# LocoNet-DCC_Interface_v2_0.net
KiCad netlist of a schematic drawn in EAGLE
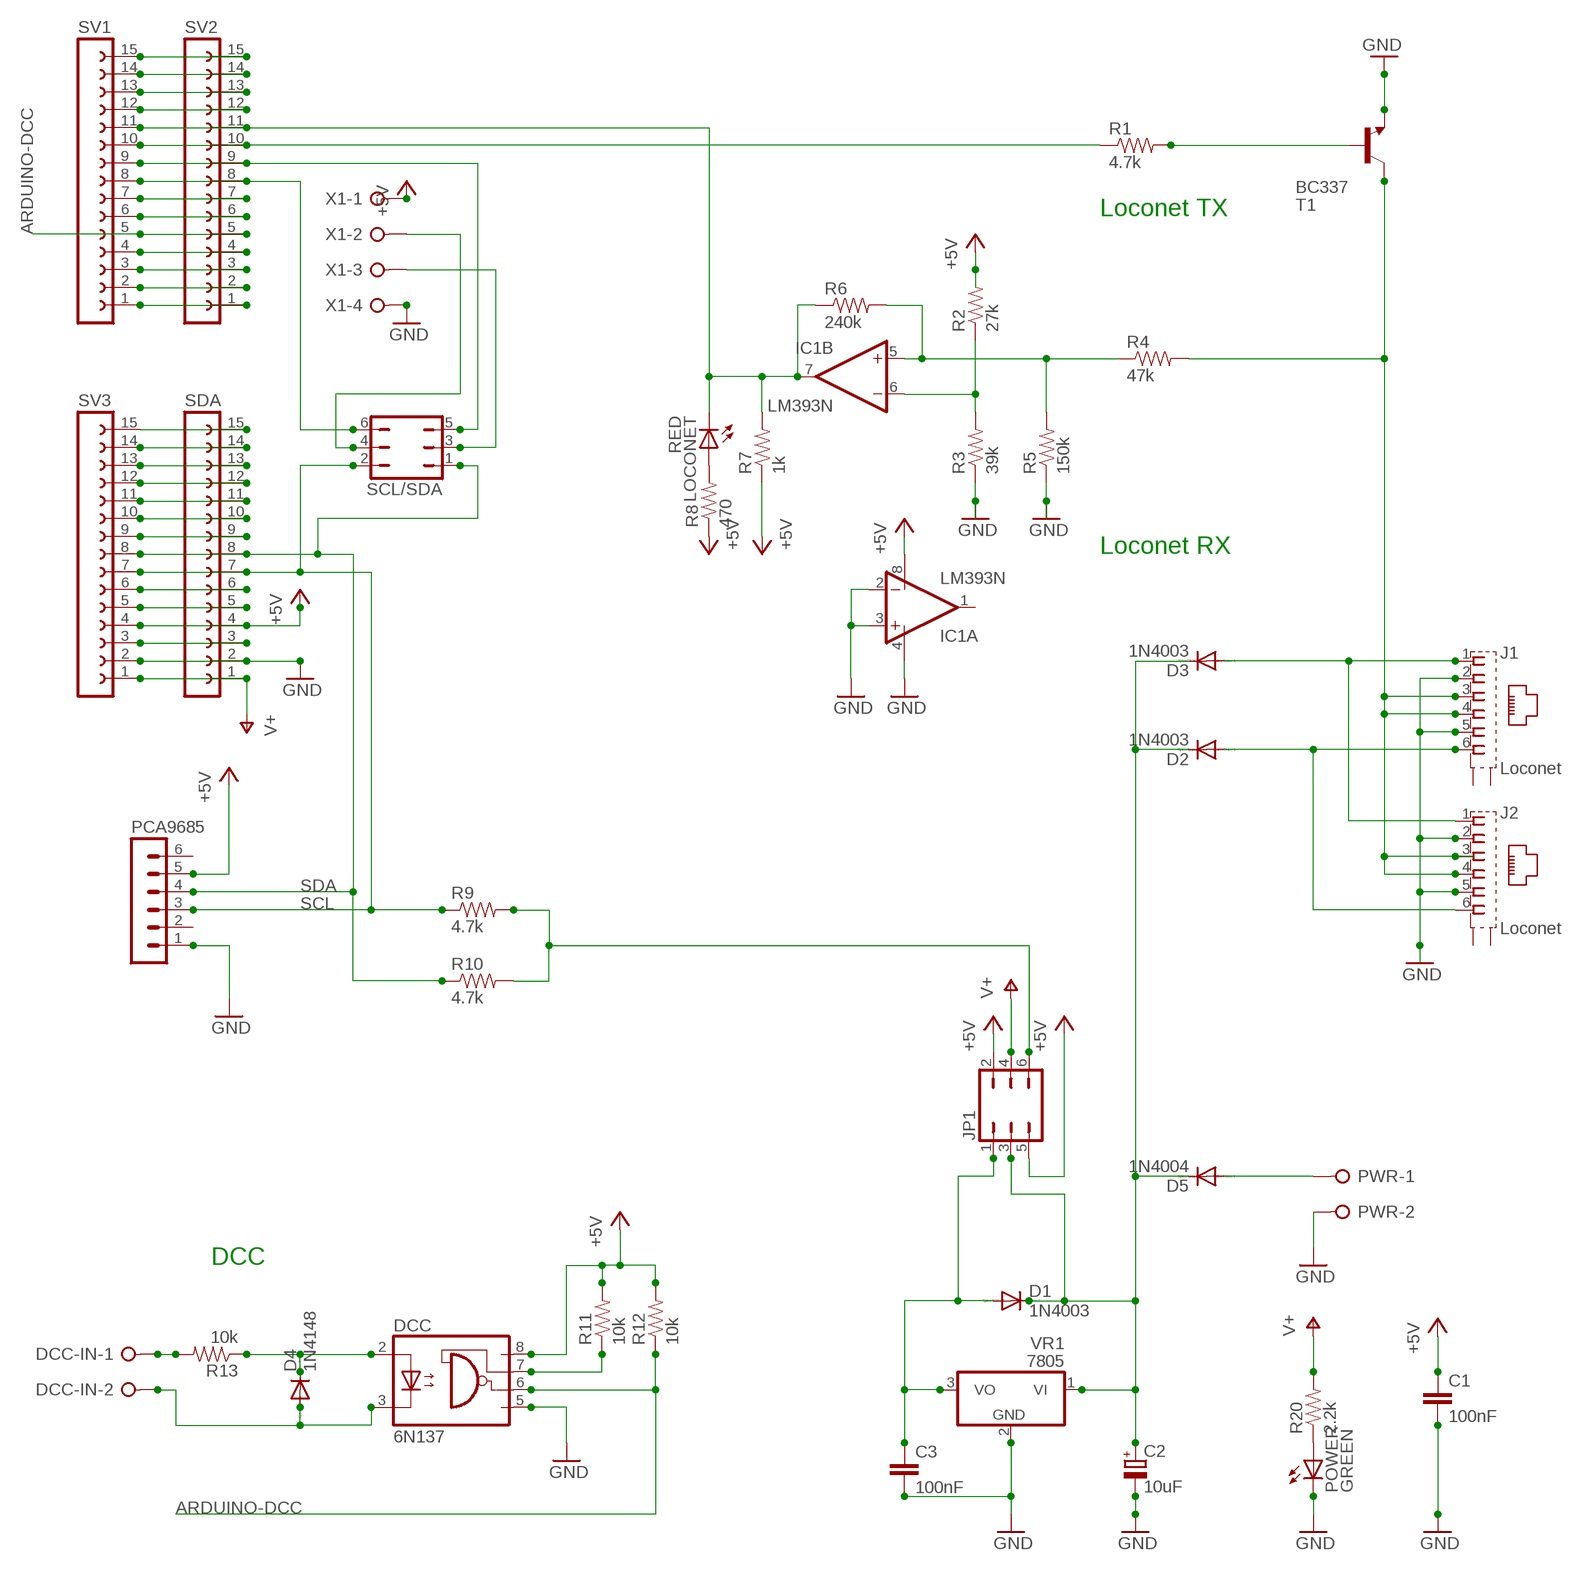
[diagram p0: schematic, sheet 1]

(export (version "E")
  (design (tool "Eeschema 10.0.6"))
  (components
    (comp (ref "C1")
      (value "100nF")
      (footprint "eagle-import:C025_050-025X075")
      (libsource (lib "eagle-import") (part "C-EU025_050-025X075"))
    )
    (comp (ref "C2")
      (value "10uF")
      (footprint "eagle-import:E2,5-6")
      (libsource (lib "eagle-import") (part "CPOL-EUE2.5-6"))
    )
    (comp (ref "C3")
      (value "100nF")
      (footprint "eagle-import:C025_050-025X075")
      (libsource (lib "eagle-import") (part "C-EU025_050-025X075"))
    )
    (comp (ref "D1")
      (value "1N4003")
      (footprint "eagle-import:DO41-10")
      (libsource (lib "eagle-import") (part "1N4004"))
    )
    (comp (ref "D2")
      (value "1N4003")
      (footprint "eagle-import:DO41-10")
      (libsource (lib "eagle-import") (part "1N4004"))
    )
    (comp (ref "D3")
      (value "1N4003")
      (footprint "eagle-import:DO41-10")
      (libsource (lib "eagle-import") (part "1N4004"))
    )
    (comp (ref "D4")
      (value "1N4148")
      (footprint "eagle-import:DO35-7")
      (libsource (lib "eagle-import") (part "1N4148DO35-7"))
    )
    (comp (ref "D5")
      (value "1N4004")
      (footprint "eagle-import:DO41-10")
      (libsource (lib "eagle-import") (part "1N4004"))
    )
    (comp (ref "DCC")
      (value "6N137")
      (footprint "eagle-import:DIL08")
      (libsource (lib "eagle-import") (part "6N137"))
    )
    (comp (ref "DCC-IN")
      (value "W237-02P")
      (footprint "eagle-import:W237-132")
      (libsource (lib "eagle-import") (part "W237-02P"))
    )
    (comp (ref "IC1")
      (value "LM393N")
      (footprint "eagle-import:DIL08")
      (libsource (lib "eagle-import") (part "LM393N"))
    )
    (comp (ref "J1")
      (value "Loconet")
      (footprint "eagle-import:555140-1")
      (libsource (lib "eagle-import") (part "555140-1"))
    )
    (comp (ref "J2")
      (value "Loconet")
      (footprint "eagle-import:555140-1")
      (libsource (lib "eagle-import") (part "555140-1"))
    )
    (comp (ref "JP1")
      (value "JP3Q")
      (footprint "eagle-import:JP3Q")
      (libsource (lib "eagle-import") (part "JP3Q"))
    )
    (comp (ref "LOCONET")
      (value "RED")
      (footprint "eagle-import:LED3MM")
      (libsource (lib "eagle-import") (part "LED3MM"))
    )
    (comp (ref "PCA9685")
      (value "MA06-1")
      (footprint "eagle-import:MA06-1")
      (libsource (lib "eagle-import") (part "MA06-1"))
    )
    (comp (ref "POWER")
      (value "GREEN")
      (footprint "eagle-import:LED3MM")
      (libsource (lib "eagle-import") (part "LED3MM"))
    )
    (comp (ref "PWR")
      (value "W237-02P")
      (footprint "eagle-import:W237-132")
      (libsource (lib "eagle-import") (part "W237-02P"))
    )
    (comp (ref "R1")
      (value "4.7k")
      (footprint "eagle-import:AXIAL-0.3")
      (libsource (lib "eagle-import") (part "RESISTORAXIAL-0.3"))
    )
    (comp (ref "R2")
      (value "27k")
      (footprint "eagle-import:AXIAL-0.3")
      (libsource (lib "eagle-import") (part "RESISTORAXIAL-0.3"))
    )
    (comp (ref "R3")
      (value "39k")
      (footprint "eagle-import:AXIAL-0.3")
      (libsource (lib "eagle-import") (part "RESISTORAXIAL-0.3"))
    )
    (comp (ref "R4")
      (value "47k")
      (footprint "eagle-import:AXIAL-0.3")
      (libsource (lib "eagle-import") (part "RESISTORAXIAL-0.3"))
    )
    (comp (ref "R5")
      (value "150k")
      (footprint "eagle-import:AXIAL-0.3")
      (libsource (lib "eagle-import") (part "RESISTORAXIAL-0.3"))
    )
    (comp (ref "R6")
      (value "240k")
      (footprint "eagle-import:AXIAL-0.3")
      (libsource (lib "eagle-import") (part "RESISTORAXIAL-0.3"))
    )
    (comp (ref "R7")
      (value "1k")
      (footprint "eagle-import:AXIAL-0.3")
      (libsource (lib "eagle-import") (part "RESISTORAXIAL-0.3"))
    )
    (comp (ref "R8")
      (value "470")
      (footprint "eagle-import:AXIAL-0.3")
      (libsource (lib "eagle-import") (part "RESISTORAXIAL-0.3"))
    )
    (comp (ref "R9")
      (value "4.7k")
      (footprint "eagle-import:AXIAL-0.3")
      (libsource (lib "eagle-import") (part "RESISTORAXIAL-0.3"))
    )
    (comp (ref "R10")
      (value "4.7k")
      (footprint "eagle-import:AXIAL-0.3")
      (libsource (lib "eagle-import") (part "RESISTORAXIAL-0.3"))
    )
    (comp (ref "R11")
      (value "10k")
      (footprint "eagle-import:AXIAL-0.3")
      (libsource (lib "eagle-import") (part "RESISTORAXIAL-0.3"))
    )
    (comp (ref "R12")
      (value "10k")
      (footprint "eagle-import:AXIAL-0.3")
      (libsource (lib "eagle-import") (part "RESISTORAXIAL-0.3"))
    )
    (comp (ref "R13")
      (value "10k")
      (footprint "eagle-import:AXIAL-0.3")
      (libsource (lib "eagle-import") (part "RESISTORAXIAL-0.3"))
    )
    (comp (ref "R20")
      (value "2.2k")
      (footprint "eagle-import:AXIAL-0.3")
      (libsource (lib "eagle-import") (part "RESISTORAXIAL-0.3"))
    )
    (comp (ref "SCL/SDA")
      (value "JP3Q")
      (footprint "eagle-import:JP3Q")
      (libsource (lib "eagle-import") (part "JP3Q"))
    )
    (comp (ref "SDA")
      (value "FE15-1NOTEXT")
      (footprint "eagle-import:FE15")
      (libsource (lib "eagle-import") (part "FE15-1NOTEXT"))
    )
    (comp (ref "SV1")
      (value "FE15-1NOTEXT")
      (footprint "eagle-import:FE15")
      (libsource (lib "eagle-import") (part "FE15-1NOTEXT"))
    )
    (comp (ref "SV2")
      (value "FE15-1NOTEXT")
      (footprint "eagle-import:FE15")
      (libsource (lib "eagle-import") (part "FE15-1NOTEXT"))
    )
    (comp (ref "SV3")
      (value "FE15-1NOTEXT")
      (footprint "eagle-import:FE15")
      (libsource (lib "eagle-import") (part "FE15-1NOTEXT"))
    )
    (comp (ref "T1")
      (value "BC337")
      (footprint "eagle-import:TO92")
      (libsource (lib "eagle-import") (part "BC337"))
    )
    (comp (ref "VR1")
      (value "7805")
      (footprint "eagle-import:TO220V")
      (libsource (lib "eagle-import") (part "78TV05"))
    )
    (comp (ref "X1")
      (value "W237-04P")
      (footprint "eagle-import:W237-4P")
      (libsource (lib "eagle-import") (part "W237-04P"))
    )
  )
  (nets
    (net (code "1") (name "+5V") (class "Default")
      (node (ref "C1") (pin "1") (pinfunction "1_1") (pintype "passive"))
      (node (ref "DCC") (pin "8") (pinfunction "VCC_8") (pintype "passive"))
      (node (ref "IC1") (pin "8") (pinfunction "V+_8") (pintype "power_in"))
      (node (ref "JP1") (pin "2") (pinfunction "2_2") (pintype "passive"))
      (node (ref "JP1") (pin "5") (pinfunction "5_5") (pintype "passive"))
      (node (ref "PCA9685") (pin "5") (pinfunction "5_5") (pintype "passive"))
      (node (ref "R11") (pin "P$2") (pinfunction "2_P$2") (pintype "passive"))
      (node (ref "R12") (pin "P$2") (pinfunction "2_P$2") (pintype "passive"))
      (node (ref "R2") (pin "P$2") (pinfunction "2_P$2") (pintype "passive"))
      (node (ref "R7") (pin "P$1") (pinfunction "1_P$1") (pintype "passive"))
      (node (ref "R8") (pin "P$1") (pinfunction "1_P$1") (pintype "passive"))
      (node (ref "SDA") (pin "4") (pinfunction "4_4") (pintype "passive"))
      (node (ref "SV3") (pin "4") (pinfunction "4_4") (pintype "passive"))
      (node (ref "X1") (pin "1") (pinfunction "KL_1") (pintype "passive"))
    )
    (net (code "2") (name "/ARDUINO-DCC") (class "Default")
      (node (ref "DCC") (pin "6") (pinfunction "VO_6") (pintype "passive"))
      (node (ref "R12") (pin "P$1") (pinfunction "1_P$1") (pintype "passive"))
      (node (ref "SV1") (pin "5") (pinfunction "5_5") (pintype "passive"))
      (node (ref "SV2") (pin "5") (pinfunction "5_5") (pintype "passive"))
    )
    (net (code "3") (name "/SCL") (class "Default")
      (node (ref "PCA9685") (pin "3") (pinfunction "3_3") (pintype "passive"))
      (node (ref "R9") (pin "P$1") (pinfunction "1_P$1") (pintype "passive"))
      (node (ref "SCL/SDA") (pin "2") (pinfunction "2_2") (pintype "passive"))
      (node (ref "SDA") (pin "7") (pinfunction "7_7") (pintype "passive"))
      (node (ref "SV3") (pin "7") (pinfunction "7_7") (pintype "passive"))
    )
    (net (code "4") (name "/SDA") (class "Default")
      (node (ref "PCA9685") (pin "4") (pinfunction "4_4") (pintype "passive"))
      (node (ref "R10") (pin "P$1") (pinfunction "1_P$1") (pintype "passive"))
      (node (ref "SCL/SDA") (pin "1") (pinfunction "1_1") (pintype "passive"))
      (node (ref "SDA") (pin "8") (pinfunction "8_8") (pintype "passive"))
      (node (ref "SV3") (pin "8") (pinfunction "8_8") (pintype "passive"))
    )
    (net (code "5") (name "GND") (class "Default")
      (node (ref "C1") (pin "2") (pinfunction "2_2") (pintype "passive"))
      (node (ref "C2") (pin "-") (pinfunction "-_-") (pintype "passive"))
      (node (ref "C3") (pin "2") (pinfunction "2_2") (pintype "passive"))
      (node (ref "DCC") (pin "5") (pinfunction "GND_5") (pintype "passive"))
      (node (ref "IC1") (pin "2") (pinfunction "-IN_2") (pintype "input"))
      (node (ref "IC1") (pin "3") (pinfunction "+IN_3") (pintype "input"))
      (node (ref "IC1") (pin "4") (pinfunction "V-_4") (pintype "power_in"))
      (node (ref "J1") (pin "2") (pinfunction "2_2") (pintype "passive"))
      (node (ref "J1") (pin "5") (pinfunction "5_5") (pintype "passive"))
      (node (ref "J2") (pin "2") (pinfunction "2_2") (pintype "passive"))
      (node (ref "J2") (pin "5") (pinfunction "5_5") (pintype "passive"))
      (node (ref "PCA9685") (pin "1") (pinfunction "1_1") (pintype "passive"))
      (node (ref "POWER") (pin "K") (pinfunction "C_K") (pintype "passive"))
      (node (ref "PWR") (pin "2") (pinfunction "KL_2") (pintype "passive"))
      (node (ref "R3") (pin "P$1") (pinfunction "1_P$1") (pintype "passive"))
      (node (ref "R5") (pin "P$1") (pinfunction "1_P$1") (pintype "passive"))
      (node (ref "SDA") (pin "2") (pinfunction "2_2") (pintype "passive"))
      (node (ref "SV3") (pin "2") (pinfunction "2_2") (pintype "passive"))
      (node (ref "T1") (pin "1") (pinfunction "E_1") (pintype "passive"))
      (node (ref "VR1") (pin "2") (pinfunction "GND_2") (pintype "passive"))
      (node (ref "X1") (pin "4") (pinfunction "KL_4") (pintype "passive"))
    )
    (net (code "6") (name "Net-(D2-PadA)") (class "Default")
      (node (ref "D2") (pin "A") (pinfunction "A_A") (pintype "passive"))
      (node (ref "J1") (pin "6") (pinfunction "6_6") (pintype "passive"))
      (node (ref "J2") (pin "6") (pinfunction "6_6") (pintype "passive"))
    )
    (net (code "7") (name "Net-(D3-PadA)") (class "Default")
      (node (ref "D3") (pin "A") (pinfunction "A_A") (pintype "passive"))
      (node (ref "J1") (pin "1") (pinfunction "1_1") (pintype "passive"))
      (node (ref "J2") (pin "1") (pinfunction "1_1") (pintype "passive"))
    )
    (net (code "8") (name "Net-(DCC-A)") (class "Default")
      (node (ref "D4") (pin "C") (pinfunction "C_C") (pintype "passive"))
      (node (ref "DCC") (pin "2") (pinfunction "A_2") (pintype "passive"))
      (node (ref "R13") (pin "P$1") (pinfunction "1_P$1") (pintype "passive"))
    )
    (net (code "9") (name "Net-(DCC-C)") (class "Default")
      (node (ref "D4") (pin "A") (pinfunction "A_A") (pintype "passive"))
      (node (ref "DCC") (pin "3") (pinfunction "C_3") (pintype "passive"))
      (node (ref "DCC-IN") (pin "2") (pinfunction "KL_2") (pintype "passive"))
    )
    (net (code "10") (name "Net-(DCC-INA-KL)") (class "Default")
      (node (ref "DCC-IN") (pin "1") (pinfunction "KL_1") (pintype "passive"))
      (node (ref "R13") (pin "P$2") (pinfunction "2_P$2") (pintype "passive"))
    )
    (net (code "11") (name "Net-(DCC-VE)") (class "Default")
      (node (ref "DCC") (pin "7") (pinfunction "VE_7") (pintype "passive"))
      (node (ref "R11") (pin "P$1") (pinfunction "1_P$1") (pintype "passive"))
    )
    (net (code "12") (name "Net-(IC1B-+IN)") (class "Default")
      (node (ref "IC1") (pin "5") (pinfunction "+IN_5") (pintype "input"))
      (node (ref "R4") (pin "P$1") (pinfunction "1_P$1") (pintype "passive"))
      (node (ref "R5") (pin "P$2") (pinfunction "2_P$2") (pintype "passive"))
      (node (ref "R6") (pin "P$2") (pinfunction "2_P$2") (pintype "passive"))
    )
    (net (code "13") (name "Net-(IC1B--IN)") (class "Default")
      (node (ref "IC1") (pin "6") (pinfunction "-IN_6") (pintype "input"))
      (node (ref "R2") (pin "P$1") (pinfunction "1_P$1") (pintype "passive"))
      (node (ref "R3") (pin "P$2") (pinfunction "2_P$2") (pintype "passive"))
    )
    (net (code "14") (name "Net-(IC1B-OUT)") (class "Default")
      (node (ref "IC1") (pin "7") (pinfunction "OUT_7") (pintype "output"))
      (node (ref "LOCONET") (pin "K") (pinfunction "C_K") (pintype "passive"))
      (node (ref "R6") (pin "P$1") (pinfunction "1_P$1") (pintype "passive"))
      (node (ref "R7") (pin "P$2") (pinfunction "2_P$2") (pintype "passive"))
      (node (ref "SV1") (pin "11") (pinfunction "11_11") (pintype "passive"))
      (node (ref "SV2") (pin "11") (pinfunction "11_11") (pintype "passive"))
    )
    (net (code "15") (name "Net-(PWRA-KL)") (class "Default")
      (node (ref "D5") (pin "A") (pinfunction "A_A") (pintype "passive"))
      (node (ref "PWR") (pin "1") (pinfunction "KL_1") (pintype "passive"))
    )
    (net (code "16") (name "Net-(R1-1)") (class "Default")
      (node (ref "R1") (pin "P$1") (pinfunction "1_P$1") (pintype "passive"))
      (node (ref "SV1") (pin "10") (pinfunction "10_10") (pintype "passive"))
      (node (ref "SV2") (pin "10") (pinfunction "10_10") (pintype "passive"))
    )
    (net (code "17") (name "Net-(R1-2)") (class "Default")
      (node (ref "R1") (pin "P$2") (pinfunction "2_P$2") (pintype "passive"))
      (node (ref "T1") (pin "2") (pinfunction "B_2") (pintype "passive"))
    )
    (net (code "18") (name "Net-(R4-2)") (class "Default")
      (node (ref "J1") (pin "3") (pinfunction "3_3") (pintype "passive"))
      (node (ref "J1") (pin "4") (pinfunction "4_4") (pintype "passive"))
      (node (ref "J2") (pin "3") (pinfunction "3_3") (pintype "passive"))
      (node (ref "J2") (pin "4") (pinfunction "4_4") (pintype "passive"))
      (node (ref "R4") (pin "P$2") (pinfunction "2_P$2") (pintype "passive"))
      (node (ref "T1") (pin "3") (pinfunction "C_3") (pintype "passive"))
    )
    (net (code "19") (name "Net-(R8-2)") (class "Default")
      (node (ref "LOCONET") (pin "A") (pinfunction "A_A") (pintype "passive"))
      (node (ref "R8") (pin "P$2") (pinfunction "2_P$2") (pintype "passive"))
    )
    (net (code "20") (name "Net-(R10-2)") (class "Default")
      (node (ref "JP1") (pin "6") (pinfunction "6_6") (pintype "passive"))
      (node (ref "R10") (pin "P$2") (pinfunction "2_P$2") (pintype "passive"))
      (node (ref "R9") (pin "P$2") (pinfunction "2_P$2") (pintype "passive"))
    )
    (net (code "21") (name "Net-(R20-1)") (class "Default")
      (node (ref "POWER") (pin "A") (pinfunction "A_A") (pintype "passive"))
      (node (ref "R20") (pin "P$1") (pinfunction "1_P$1") (pintype "passive"))
    )
    (net (code "22") (name "Net-(SCL/SDA-Pad5)") (class "Default")
      (node (ref "SCL/SDA") (pin "5") (pinfunction "5_5") (pintype "passive"))
      (node (ref "SV1") (pin "9") (pinfunction "9_9") (pintype "passive"))
      (node (ref "SV2") (pin "9") (pinfunction "9_9") (pintype "passive"))
    )
    (net (code "23") (name "Net-(SCL/SDA-Pad6)") (class "Default")
      (node (ref "SCL/SDA") (pin "6") (pinfunction "6_6") (pintype "passive"))
      (node (ref "SV1") (pin "8") (pinfunction "8_8") (pintype "passive"))
      (node (ref "SV2") (pin "8") (pinfunction "8_8") (pintype "passive"))
    )
    (net (code "24") (name "Net-(SDA-Pad3)") (class "Default")
      (node (ref "SDA") (pin "3") (pinfunction "3_3") (pintype "passive"))
      (node (ref "SV3") (pin "3") (pinfunction "3_3") (pintype "passive"))
    )
    (net (code "25") (name "Net-(SDA-Pad5)") (class "Default")
      (node (ref "SDA") (pin "5") (pinfunction "5_5") (pintype "passive"))
      (node (ref "SV3") (pin "5") (pinfunction "5_5") (pintype "passive"))
    )
    (net (code "26") (name "Net-(SDA-Pad6)") (class "Default")
      (node (ref "SDA") (pin "6") (pinfunction "6_6") (pintype "passive"))
      (node (ref "SV3") (pin "6") (pinfunction "6_6") (pintype "passive"))
    )
    (net (code "27") (name "Net-(SDA-Pad9)") (class "Default")
      (node (ref "SDA") (pin "9") (pinfunction "9_9") (pintype "passive"))
      (node (ref "SV3") (pin "9") (pinfunction "9_9") (pintype "passive"))
    )
    (net (code "28") (name "Net-(SDA-Pad10)") (class "Default")
      (node (ref "SDA") (pin "10") (pinfunction "10_10") (pintype "passive"))
      (node (ref "SV3") (pin "10") (pinfunction "10_10") (pintype "passive"))
    )
    (net (code "29") (name "Net-(SDA-Pad11)") (class "Default")
      (node (ref "SDA") (pin "11") (pinfunction "11_11") (pintype "passive"))
      (node (ref "SV3") (pin "11") (pinfunction "11_11") (pintype "passive"))
    )
    (net (code "30") (name "Net-(SDA-Pad12)") (class "Default")
      (node (ref "SDA") (pin "12") (pinfunction "12_12") (pintype "passive"))
      (node (ref "SV3") (pin "12") (pinfunction "12_12") (pintype "passive"))
    )
    (net (code "31") (name "Net-(SDA-Pad13)") (class "Default")
      (node (ref "SDA") (pin "13") (pinfunction "13_13") (pintype "passive"))
      (node (ref "SV3") (pin "13") (pinfunction "13_13") (pintype "passive"))
    )
    (net (code "32") (name "Net-(SDA-Pad14)") (class "Default")
      (node (ref "SDA") (pin "14") (pinfunction "14_14") (pintype "passive"))
      (node (ref "SV3") (pin "14") (pinfunction "14_14") (pintype "passive"))
    )
    (net (code "33") (name "Net-(SDA-Pad15)") (class "Default")
      (node (ref "SDA") (pin "15") (pinfunction "15_15") (pintype "passive"))
      (node (ref "SV3") (pin "15") (pinfunction "15_15") (pintype "passive"))
    )
    (net (code "34") (name "Net-(SV1-Pad1)") (class "Default")
      (node (ref "SV1") (pin "1") (pinfunction "1_1") (pintype "passive"))
      (node (ref "SV2") (pin "1") (pinfunction "1_1") (pintype "passive"))
    )
    (net (code "35") (name "Net-(SV1-Pad2)") (class "Default")
      (node (ref "SV1") (pin "2") (pinfunction "2_2") (pintype "passive"))
      (node (ref "SV2") (pin "2") (pinfunction "2_2") (pintype "passive"))
    )
    (net (code "36") (name "Net-(SV1-Pad3)") (class "Default")
      (node (ref "SV1") (pin "3") (pinfunction "3_3") (pintype "passive"))
      (node (ref "SV2") (pin "3") (pinfunction "3_3") (pintype "passive"))
    )
    (net (code "37") (name "Net-(SV1-Pad4)") (class "Default")
      (node (ref "SV1") (pin "4") (pinfunction "4_4") (pintype "passive"))
      (node (ref "SV2") (pin "4") (pinfunction "4_4") (pintype "passive"))
    )
    (net (code "38") (name "Net-(SV1-Pad6)") (class "Default")
      (node (ref "SV1") (pin "6") (pinfunction "6_6") (pintype "passive"))
      (node (ref "SV2") (pin "6") (pinfunction "6_6") (pintype "passive"))
    )
    (net (code "39") (name "Net-(SV1-Pad7)") (class "Default")
      (node (ref "SV1") (pin "7") (pinfunction "7_7") (pintype "passive"))
      (node (ref "SV2") (pin "7") (pinfunction "7_7") (pintype "passive"))
    )
    (net (code "40") (name "Net-(SV1-Pad12)") (class "Default")
      (node (ref "SV1") (pin "12") (pinfunction "12_12") (pintype "passive"))
      (node (ref "SV2") (pin "12") (pinfunction "12_12") (pintype "passive"))
    )
    (net (code "41") (name "Net-(SV1-Pad13)") (class "Default")
      (node (ref "SV1") (pin "13") (pinfunction "13_13") (pintype "passive"))
      (node (ref "SV2") (pin "13") (pinfunction "13_13") (pintype "passive"))
    )
    (net (code "42") (name "Net-(SV1-Pad14)") (class "Default")
      (node (ref "SV1") (pin "14") (pinfunction "14_14") (pintype "passive"))
      (node (ref "SV2") (pin "14") (pinfunction "14_14") (pintype "passive"))
    )
    (net (code "43") (name "Net-(SV1-Pad15)") (class "Default")
      (node (ref "SV1") (pin "15") (pinfunction "15_15") (pintype "passive"))
      (node (ref "SV2") (pin "15") (pinfunction "15_15") (pintype "passive"))
    )
    (net (code "44") (name "Net-(VR1-VI)") (class "Default")
      (node (ref "C2") (pin "+") (pinfunction "+_+") (pintype "passive"))
      (node (ref "D1") (pin "C") (pinfunction "C_C") (pintype "passive"))
      (node (ref "D2") (pin "C") (pinfunction "C_C") (pintype "passive"))
      (node (ref "D3") (pin "C") (pinfunction "C_C") (pintype "passive"))
      (node (ref "D5") (pin "C") (pinfunction "C_C") (pintype "passive"))
      (node (ref "JP1") (pin "3") (pinfunction "3_3") (pintype "passive"))
      (node (ref "VR1") (pin "1") (pinfunction "VI_1") (pintype "input"))
    )
    (net (code "45") (name "Net-(VR1-VO)") (class "Default")
      (node (ref "C3") (pin "1") (pinfunction "1_1") (pintype "passive"))
      (node (ref "D1") (pin "A") (pinfunction "A_A") (pintype "passive"))
      (node (ref "JP1") (pin "1") (pinfunction "1_1") (pintype "passive"))
      (node (ref "VR1") (pin "3") (pinfunction "VO_3") (pintype "passive"))
    )
    (net (code "46") (name "Net-(X1B-KL)") (class "Default")
      (node (ref "SCL/SDA") (pin "4") (pinfunction "4_4") (pintype "passive"))
      (node (ref "X1") (pin "2") (pinfunction "KL_2") (pintype "passive"))
    )
    (net (code "47") (name "Net-(X1C-KL)") (class "Default")
      (node (ref "SCL/SDA") (pin "3") (pinfunction "3_3") (pintype "passive"))
      (node (ref "X1") (pin "3") (pinfunction "KL_3") (pintype "passive"))
    )
    (net (code "48") (name "V+") (class "Default")
      (node (ref "JP1") (pin "4") (pinfunction "4_4") (pintype "passive"))
      (node (ref "R20") (pin "P$2") (pinfunction "2_P$2") (pintype "passive"))
      (node (ref "SDA") (pin "1") (pinfunction "1_1") (pintype "passive"))
      (node (ref "SV3") (pin "1") (pinfunction "1_1") (pintype "passive"))
    )
    (net (code "49") (name "unconnected-(IC1A-OUT-Pad1)") (class "Default")
      (node (ref "IC1") (pin "1") (pinfunction "OUT_1") (pintype "output"))
    )
    (net (code "50") (name "unconnected-(J1-S1-PadG1)") (class "Default")
      (node (ref "J1") (pin "G1") (pinfunction "S1_G1") (pintype "passive"))
    )
    (net (code "51") (name "unconnected-(J1-S2-PadG2)") (class "Default")
      (node (ref "J1") (pin "G2") (pinfunction "S2_G2") (pintype "passive"))
    )
    (net (code "52") (name "unconnected-(J2-S1-PadG1)") (class "Default")
      (node (ref "J2") (pin "G1") (pinfunction "S1_G1") (pintype "passive"))
    )
    (net (code "53") (name "unconnected-(J2-S2-PadG2)") (class "Default")
      (node (ref "J2") (pin "G2") (pinfunction "S2_G2") (pintype "passive"))
    )
    (net (code "54") (name "unconnected-(PCA9685-Pad2)") (class "Default")
      (node (ref "PCA9685") (pin "2") (pinfunction "2_2") (pintype "passive"))
    )
    (net (code "55") (name "unconnected-(PCA9685-Pad6)") (class "Default")
      (node (ref "PCA9685") (pin "6") (pinfunction "6_6") (pintype "passive"))
    )
  )
)
